# Trinket_Shield_battery.net
KiCad netlist of a schematic drawn in EAGLE
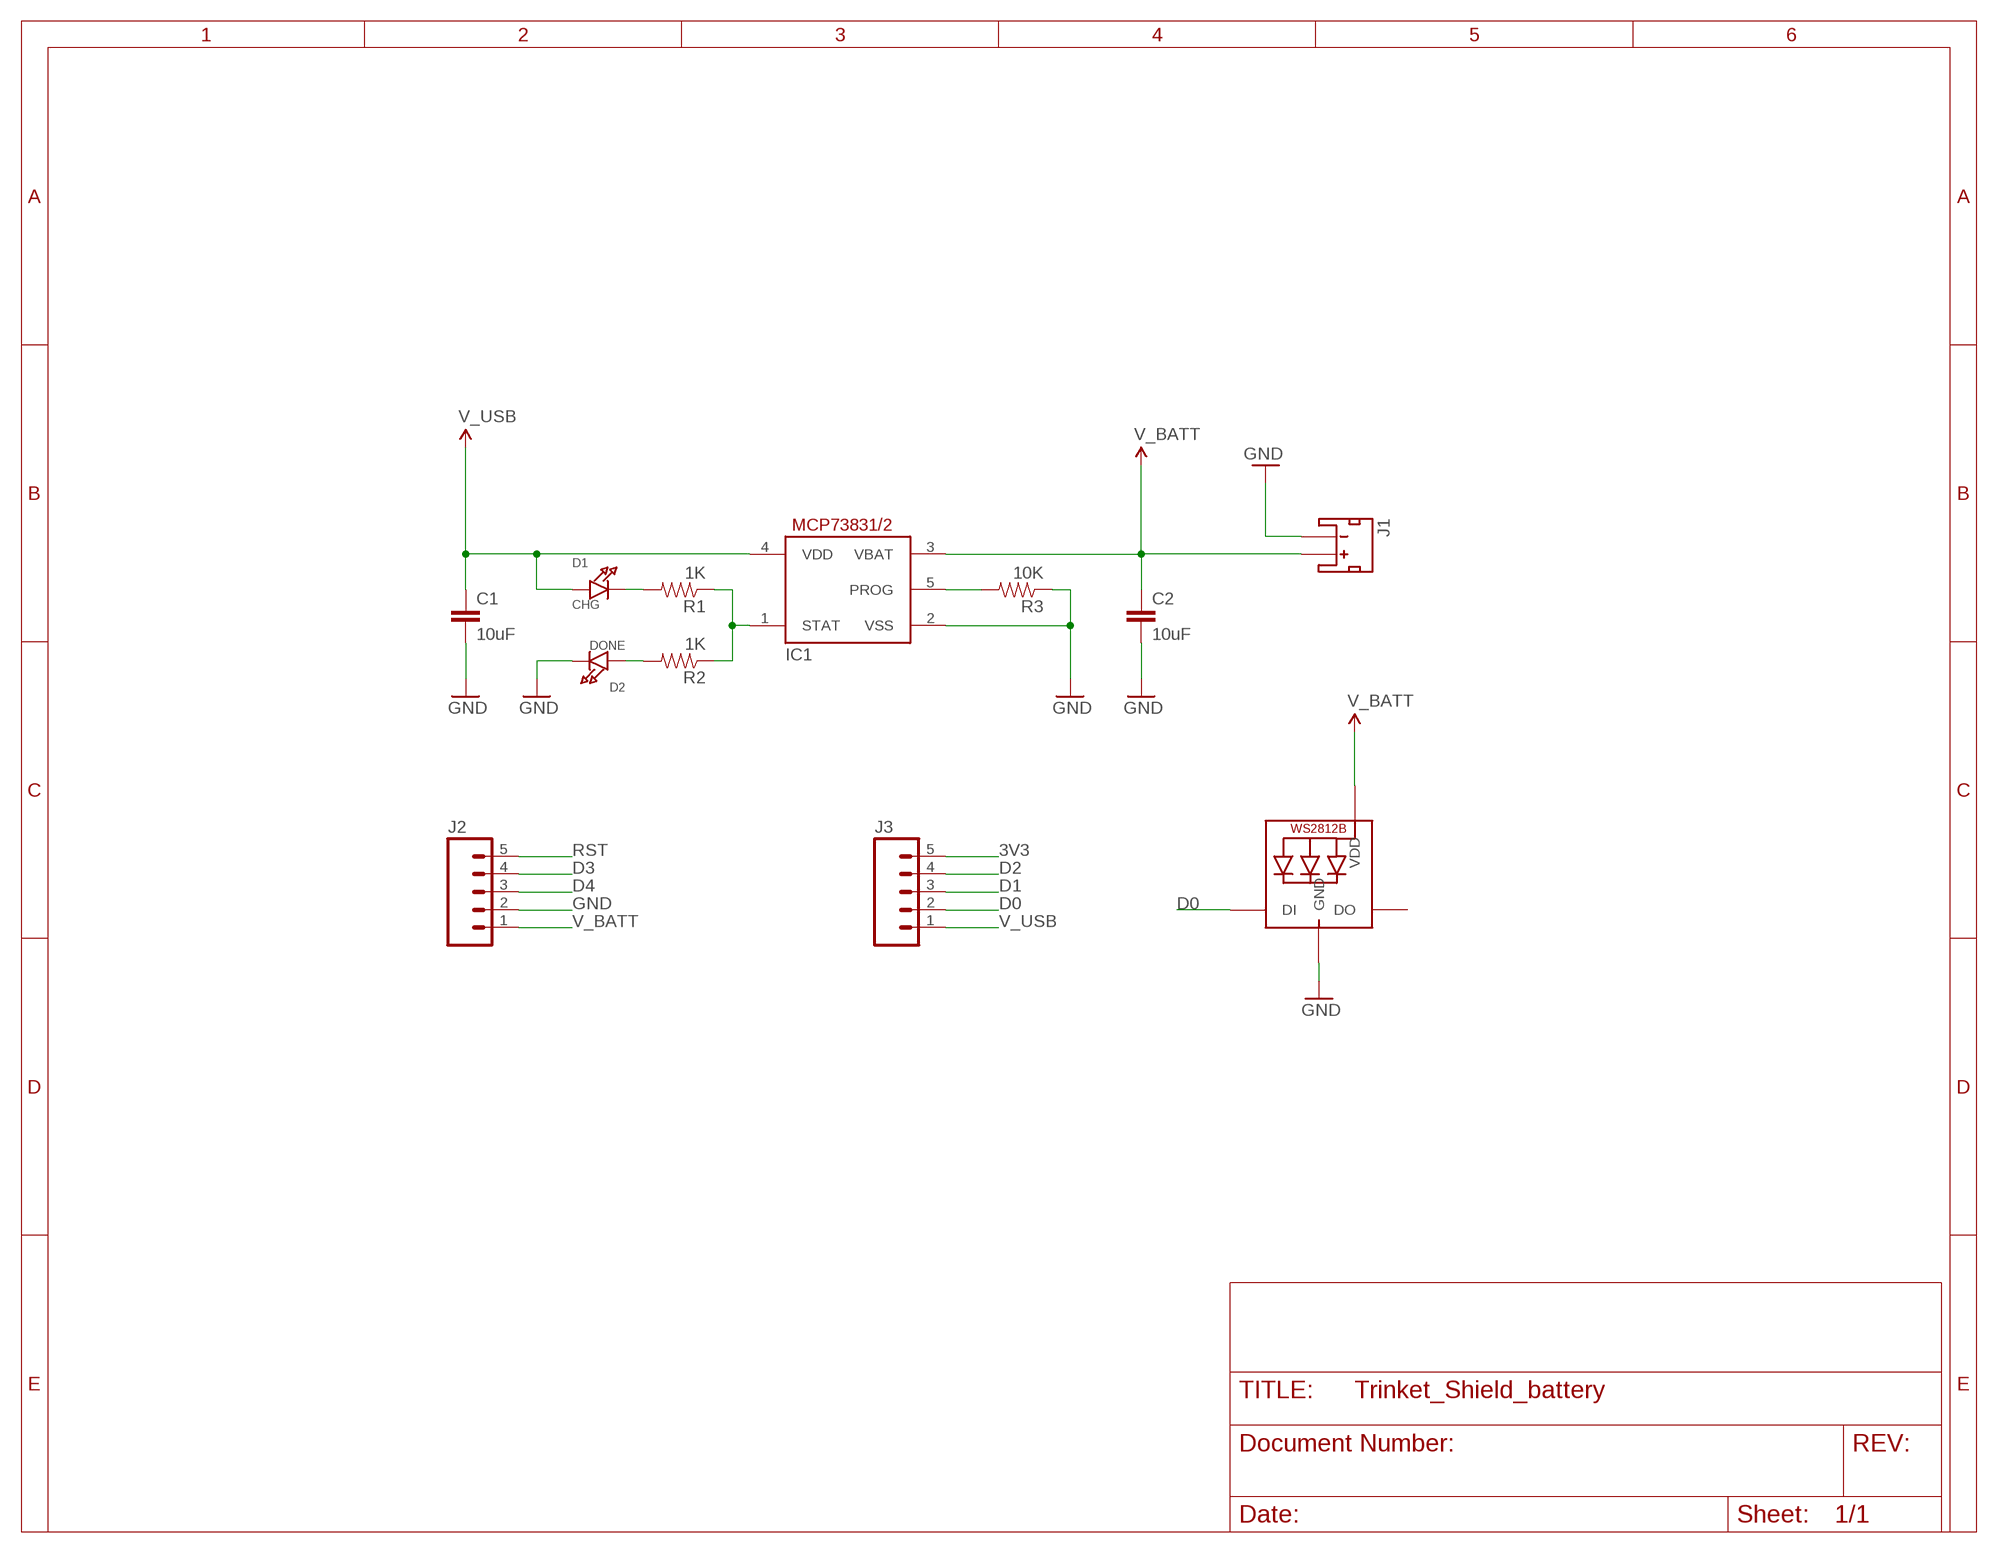
[diagram p0: schematic, sheet 1]

(export (version "E")
  (design (tool "Eeschema 10.0.6"))
  (components
    (comp (ref "C1")
      (value "10uF")
      (footprint "eagle-import:0805")
      (libsource (lib "eagle-import") (part "CAP0805"))
    )
    (comp (ref "C2")
      (value "10uF")
      (footprint "eagle-import:0805")
      (libsource (lib "eagle-import") (part "CAP0805"))
    )
    (comp (ref "D1")
      (value "CHG")
      (footprint "eagle-import:CHIPLED_0805_NOOUTLINE")
      (libsource (lib "eagle-import") (part "LED0805_NOOUTLINE"))
    )
    (comp (ref "D2")
      (value "DONE")
      (footprint "eagle-import:CHIPLED_0805_NOOUTLINE")
      (libsource (lib "eagle-import") (part "LED0805_NOOUTLINE"))
    )
    (comp (ref "IC1")
      (value "MCP73831/OT")
      (footprint "eagle-import:SOT23-5L")
      (libsource (lib "eagle-import") (part "MCP73831/OT"))
    )
    (comp (ref "J1")
      (value "JST_2MM_MALE")
      (footprint "eagle-import:JST-2-SMD")
      (libsource (lib "eagle-import") (part "JST_2MM_MALE"))
    )
    (comp (ref "J2")
      (value "M05NO_SILK")
      (footprint "eagle-import:1X05_NO_SILK")
      (libsource (lib "eagle-import") (part "M05NO_SILK"))
    )
    (comp (ref "J3")
      (value "M05NO_SILK")
      (footprint "eagle-import:1X05_NO_SILK")
      (libsource (lib "eagle-import") (part "M05NO_SILK"))
    )
    (comp (ref "LED")
      (value "WS2812B5050")
      (footprint "eagle-import:WS2812B")
      (libsource (lib "eagle-import") (part "WS2812B5050"))
    )
    (comp (ref "R1")
      (value "1K")
      (footprint "eagle-import:0805")
      (libsource (lib "eagle-import") (part "RESISTOR0805-RES"))
    )
    (comp (ref "R2")
      (value "1K")
      (footprint "eagle-import:0805")
      (libsource (lib "eagle-import") (part "RESISTOR0805-RES"))
    )
    (comp (ref "R3")
      (value "10K")
      (footprint "eagle-import:0805")
      (libsource (lib "eagle-import") (part "RESISTOR0805-RES"))
    )
  )
  (nets
    (net (code "1") (name "/3V3") (class "Default")
      (node (ref "J3") (pin "5") (pinfunction "5_5") (pintype "passive"))
    )
    (net (code "2") (name "/D0") (class "Default")
      (node (ref "J3") (pin "2") (pinfunction "2_2") (pintype "passive"))
      (node (ref "LED") (pin "4-DIN") (pinfunction "DI_4-DIN") (pintype "input"))
    )
    (net (code "3") (name "/D1") (class "Default")
      (node (ref "J3") (pin "3") (pinfunction "3_3") (pintype "passive"))
    )
    (net (code "4") (name "/D2") (class "Default")
      (node (ref "J3") (pin "4") (pinfunction "4_4") (pintype "passive"))
    )
    (net (code "5") (name "/D3") (class "Default")
      (node (ref "J2") (pin "4") (pinfunction "4_4") (pintype "passive"))
    )
    (net (code "6") (name "/D4") (class "Default")
      (node (ref "J2") (pin "3") (pinfunction "3_3") (pintype "passive"))
    )
    (net (code "7") (name "/RST") (class "Default")
      (node (ref "J2") (pin "5") (pinfunction "5_5") (pintype "passive"))
    )
    (net (code "8") (name "GND") (class "Default")
      (node (ref "C1") (pin "2") (pinfunction "2_2") (pintype "passive"))
      (node (ref "C2") (pin "2") (pinfunction "2_2") (pintype "passive"))
      (node (ref "D2") (pin "C") (pinfunction "C_C") (pintype "passive"))
      (node (ref "IC1") (pin "2") (pinfunction "VSS_2") (pintype "power_in"))
      (node (ref "J1") (pin "1") (pinfunction "-_1") (pintype "bidirectional"))
      (node (ref "J2") (pin "2") (pinfunction "2_2") (pintype "passive"))
      (node (ref "LED") (pin "3-GND") (pinfunction "GND_3-GND") (pintype "power_in"))
      (node (ref "R3") (pin "1") (pinfunction "1_1") (pintype "passive"))
    )
    (net (code "9") (name "Net-(D1-PadC)") (class "Default")
      (node (ref "D1") (pin "C") (pinfunction "C_C") (pintype "passive"))
      (node (ref "R1") (pin "2") (pinfunction "2_2") (pintype "passive"))
    )
    (net (code "10") (name "Net-(D2-PadA)") (class "Default")
      (node (ref "D2") (pin "A") (pinfunction "A_A") (pintype "passive"))
      (node (ref "R2") (pin "2") (pinfunction "2_2") (pintype "passive"))
    )
    (net (code "11") (name "Net-(IC1-PROG)") (class "Default")
      (node (ref "IC1") (pin "5") (pinfunction "PROG_5") (pintype "input"))
      (node (ref "R3") (pin "2") (pinfunction "2_2") (pintype "passive"))
    )
    (net (code "12") (name "Net-(IC1-STAT)") (class "Default")
      (node (ref "IC1") (pin "1") (pinfunction "STAT_1") (pintype "output"))
      (node (ref "R1") (pin "1") (pinfunction "1_1") (pintype "passive"))
      (node (ref "R2") (pin "1") (pinfunction "1_1") (pintype "passive"))
    )
    (net (code "13") (name "V_BATT") (class "Default")
      (node (ref "C2") (pin "1") (pinfunction "1_1") (pintype "passive"))
      (node (ref "IC1") (pin "3") (pinfunction "VBAT_3") (pintype "bidirectional"))
      (node (ref "J1") (pin "2") (pinfunction "+_2") (pintype "bidirectional"))
      (node (ref "J2") (pin "1") (pinfunction "1_1") (pintype "passive"))
      (node (ref "LED") (pin "1-VDD") (pinfunction "VDD_1-VDD") (pintype "power_in"))
    )
    (net (code "14") (name "V_USB") (class "Default")
      (node (ref "C1") (pin "1") (pinfunction "1_1") (pintype "passive"))
      (node (ref "D1") (pin "A") (pinfunction "A_A") (pintype "passive"))
      (node (ref "IC1") (pin "4") (pinfunction "VDD_4") (pintype "power_in"))
      (node (ref "J3") (pin "1") (pinfunction "1_1") (pintype "passive"))
    )
    (net (code "15") (name "unconnected-(J1-PAD1-PadNC1)") (class "Default")
      (node (ref "J1") (pin "NC1") (pinfunction "PAD1_NC1") (pintype "bidirectional"))
    )
    (net (code "16") (name "unconnected-(J1-PAD2-PadNC2)") (class "Default")
      (node (ref "J1") (pin "NC2") (pinfunction "PAD2_NC2") (pintype "bidirectional"))
    )
    (net (code "17") (name "unconnected-(LED-DO-Pad2-DOUT)") (class "Default")
      (node (ref "LED") (pin "2-DOUT") (pinfunction "DO_2-DOUT") (pintype "output"))
    )
  )
)
